# MB_Conn.net
KiCad netlist of a schematic drawn in Altium Designer
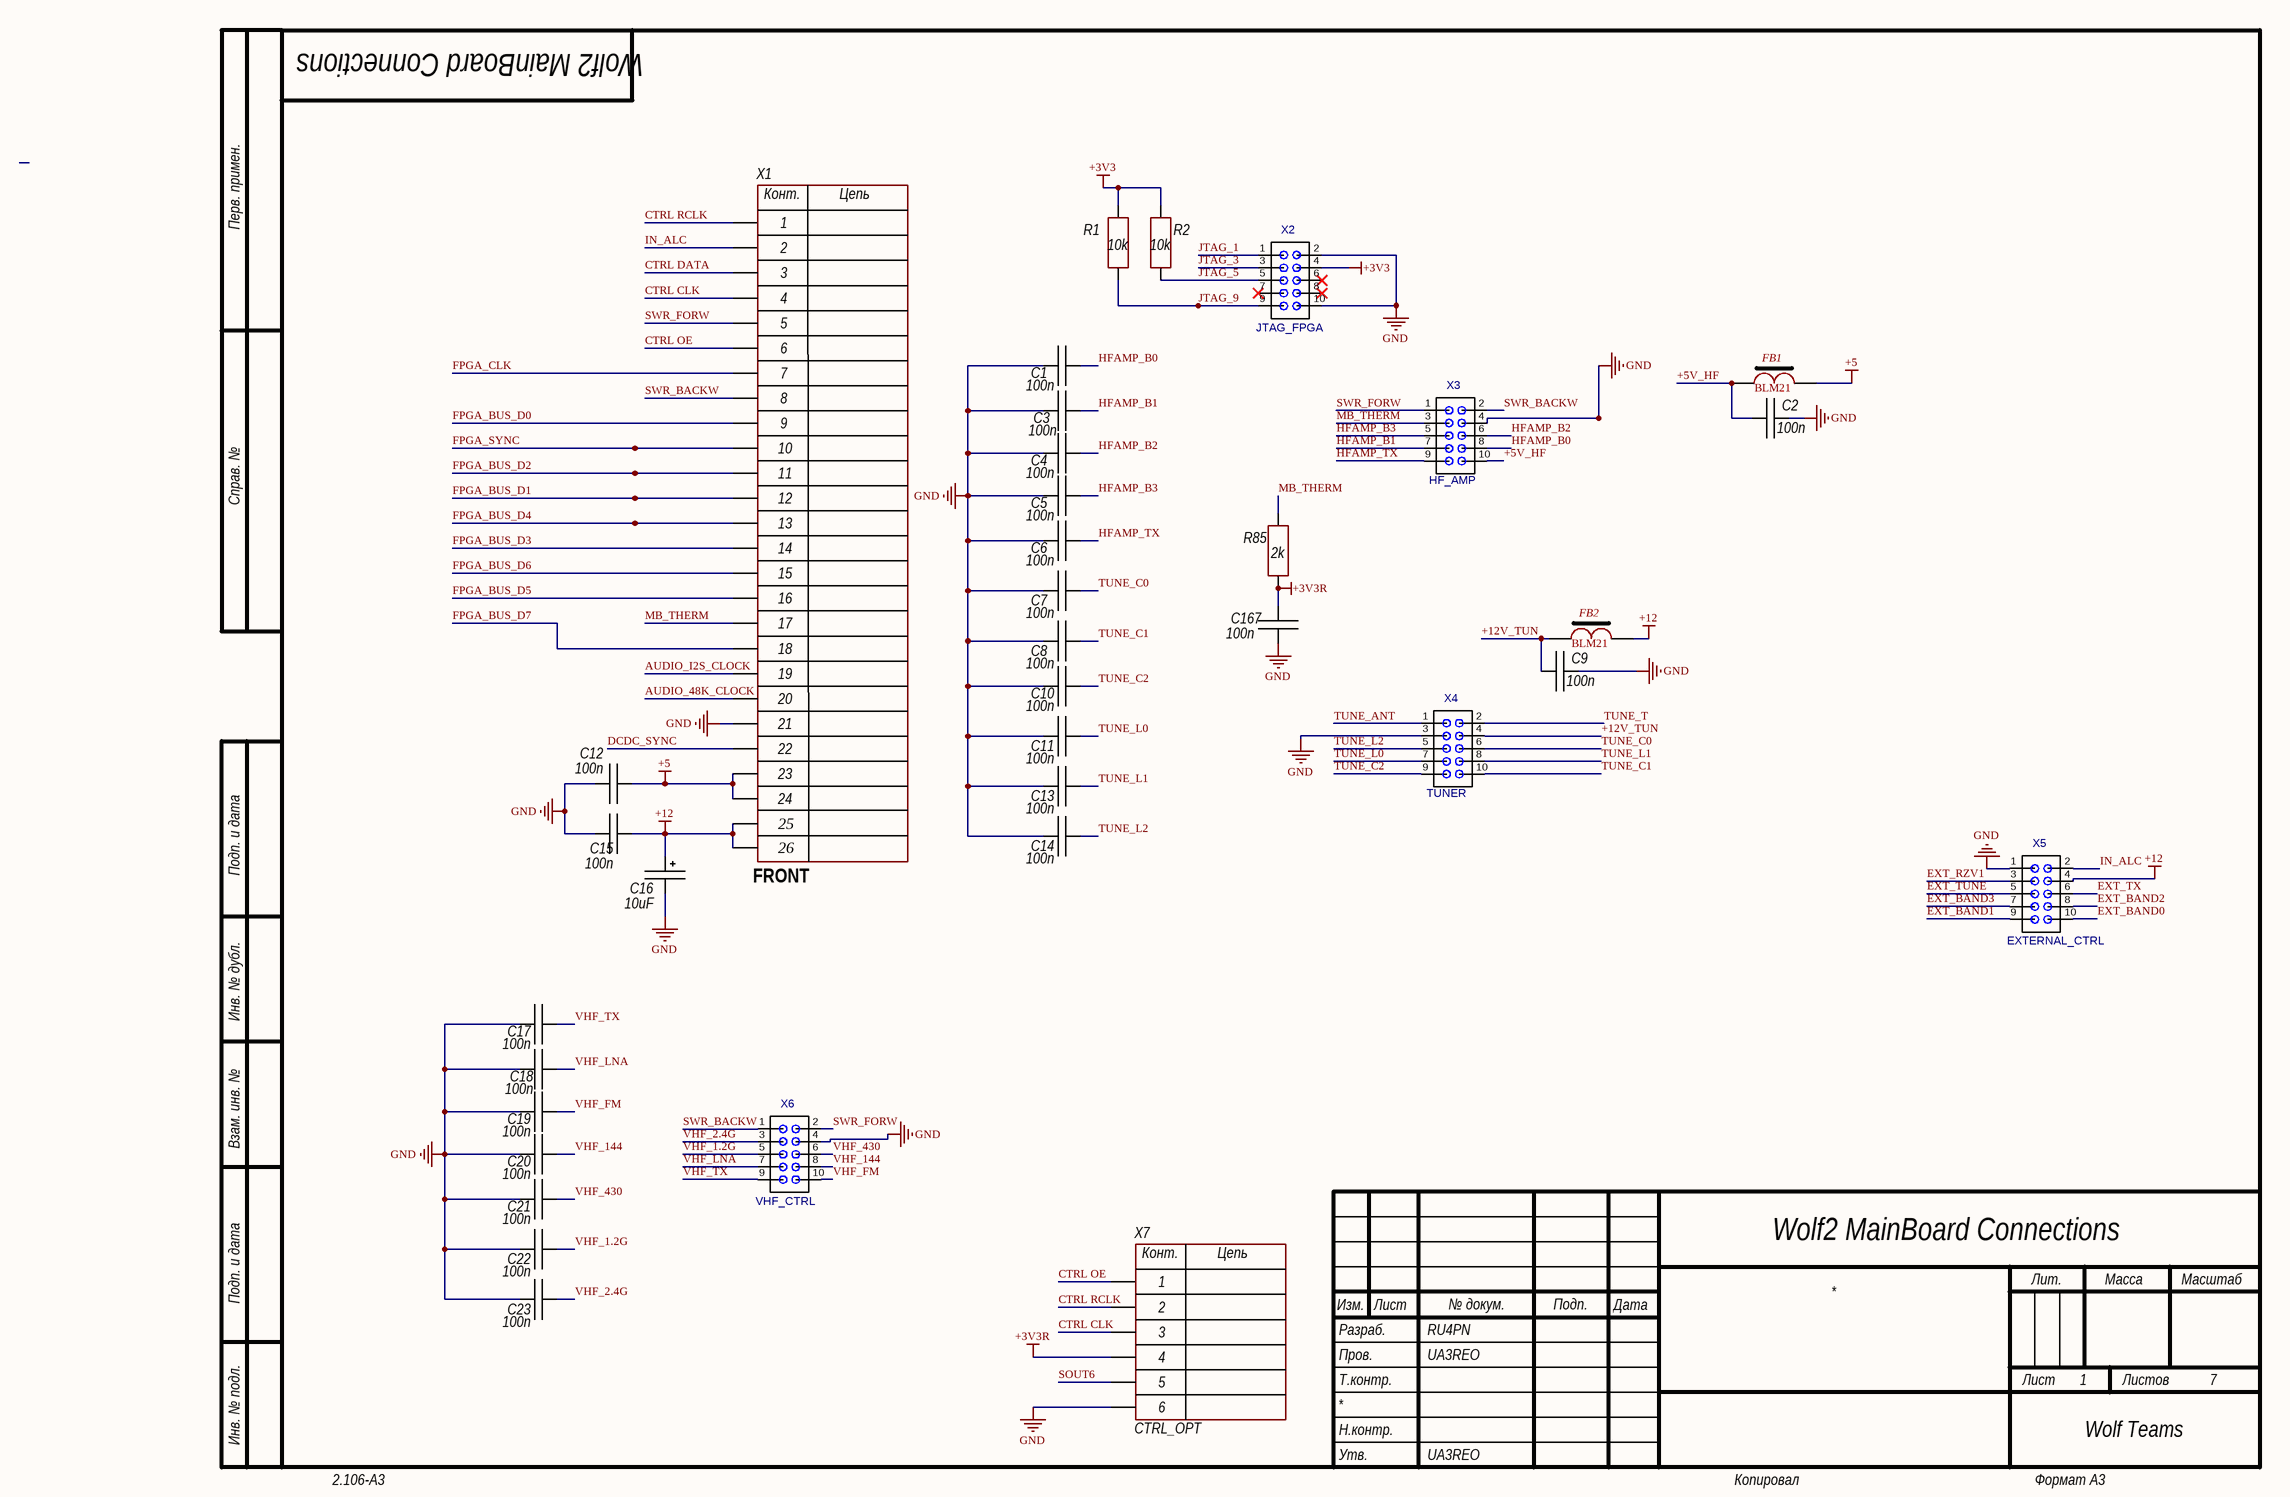
[diagram p0: MB_Conn.SchDoc]

(export (version "E")
  (design (tool "Eeschema 10.0.6"))
  (components
    (comp (ref "C1")
      (value "100n")
      (footprint "standard:CH0805C")
      (libsource (lib "Discrete") (part "Capacitor"))
    )
    (comp (ref "C2")
      (value "100n")
      (footprint "standard:CH0805C")
      (libsource (lib "Discrete") (part "Capacitor"))
    )
    (comp (ref "C3")
      (value "100n")
      (footprint "standard:CH0805C")
      (libsource (lib "Discrete") (part "Capacitor"))
    )
    (comp (ref "C4")
      (value "100n")
      (footprint "standard:CH0805C")
      (libsource (lib "Discrete") (part "Capacitor"))
    )
    (comp (ref "C5")
      (value "100n")
      (footprint "standard:CH0805C")
      (libsource (lib "Discrete") (part "Capacitor"))
    )
    (comp (ref "C6")
      (value "100n")
      (footprint "standard:CH0805C")
      (libsource (lib "Discrete") (part "Capacitor"))
    )
    (comp (ref "C7")
      (value "100n")
      (footprint "standard:CH0805C")
      (libsource (lib "Discrete") (part "Capacitor"))
    )
    (comp (ref "C8")
      (value "100n")
      (footprint "standard:CH0805C")
      (libsource (lib "Discrete") (part "Capacitor"))
    )
    (comp (ref "C9")
      (value "100n")
      (footprint "standard:CH0805C")
      (libsource (lib "Discrete") (part "Capacitor"))
    )
    (comp (ref "C10")
      (value "100n")
      (footprint "standard:CH0805C")
      (libsource (lib "Discrete") (part "Capacitor"))
    )
    (comp (ref "C11")
      (value "100n")
      (footprint "standard:CH0805C")
      (libsource (lib "Discrete") (part "Capacitor"))
    )
    (comp (ref "C12")
      (value "100n")
      (footprint "standard:CH0805C")
      (libsource (lib "Discrete") (part "Capacitor"))
    )
    (comp (ref "C13")
      (value "100n")
      (footprint "standard:CH0805C")
      (libsource (lib "Discrete") (part "Capacitor"))
    )
    (comp (ref "C14")
      (value "100n")
      (footprint "standard:CH0805C")
      (libsource (lib "Discrete") (part "Capacitor"))
    )
    (comp (ref "C15")
      (value "100n")
      (footprint "standard:CH0805C")
      (libsource (lib "Discrete") (part "Capacitor"))
    )
    (comp (ref "C16")
      (value "10uF")
      (footprint "standard:TANTAL_B")
      (libsource (lib "Discrete") (part "TantalCap"))
    )
    (comp (ref "C17")
      (value "100n")
      (footprint "standard:CH0805C")
      (libsource (lib "Discrete") (part "Capacitor"))
    )
    (comp (ref "C18")
      (value "100n")
      (footprint "standard:CH0805C")
      (libsource (lib "Discrete") (part "Capacitor"))
    )
    (comp (ref "C19")
      (value "100n")
      (footprint "standard:CH0805C")
      (libsource (lib "Discrete") (part "Capacitor"))
    )
    (comp (ref "C20")
      (value "100n")
      (footprint "standard:CH0805C")
      (libsource (lib "Discrete") (part "Capacitor"))
    )
    (comp (ref "C21")
      (value "100n")
      (footprint "standard:CH0805C")
      (libsource (lib "Discrete") (part "Capacitor"))
    )
    (comp (ref "C22")
      (value "100n")
      (footprint "standard:CH0805C")
      (libsource (lib "Discrete") (part "Capacitor"))
    )
    (comp (ref "C23")
      (value "100n")
      (footprint "standard:CH0805C")
      (libsource (lib "Discrete") (part "Capacitor"))
    )
    (comp (ref "C167")
      (value "100n")
      (footprint "standard:CH0805C")
      (libsource (lib "Discrete") (part "Capacitor"))
    )
    (comp (ref "FB1") (value "BLM21") (footprint "CH0805L") (libsource (lib "Discrete") (part "FB-1")))
    (comp (ref "FB2") (value "BLM21") (footprint "CH0805L") (libsource (lib "Discrete") (part "FB-1")))
    (comp (ref "R1") (value "10k") (footprint "standard:CH0805R") (libsource (lib "") (part "Resistor_1")))
    (comp (ref "R2") (value "10k") (footprint "standard:CH0805R") (libsource (lib "") (part "Resistor_1")))
    (comp (ref "R85")
      (value "2k")
      (footprint "standard:CH0805R")
      (libsource (lib "Discrete") (part "Resistor"))
    )
    (comp (ref "X1")
      (value "FRONT")
      (footprint "CON: IDC-26")
      (libsource (lib "Connectors") (part "26-Connector"))
    )
    (comp (ref "X2")
      (value "JTAG_FPGA")
      (footprint "CON: BH-10")
      (description "2*5 Pin")
      (libsource (lib "*") (part "IDC10"))
    )
    (comp (ref "X3")
      (value "HF_AMP")
      (footprint "CON: BH-10")
      (description "2*5 Pin")
      (libsource (lib "*") (part "IDC10"))
    )
    (comp (ref "X4")
      (value "TUNER")
      (footprint "CON: BH-10")
      (description "2*5 Pin")
      (libsource (lib "*") (part "IDC10"))
    )
    (comp (ref "X5")
      (value "EXTERNAL_CTRL")
      (footprint "CON: BH-10")
      (description "2*5 Pin")
      (libsource (lib "*") (part "IDC10"))
    )
    (comp (ref "X6")
      (value "VHF_CTRL")
      (footprint "CON: BH-10")
      (description "2*5 Pin")
      (libsource (lib "*") (part "IDC10"))
    )
    (comp (ref "X7")
      (value "CTRL_OPT")
      (footprint "custom:CON: PBS-6")
      (libsource (lib "Connectors") (part "6-Connector"))
    )
  )
  (nets
    (net (code "1") (name "+3V3") (class "Default")
      (node (ref "R1") (pin "2") (pinfunction "2_2") (pintype "passive"))
      (node (ref "R2") (pin "2") (pinfunction "2_2") (pintype "passive"))
      (node (ref "X2") (pin "4") (pinfunction "4_4") (pintype "passive"))
    )
    (net (code "2") (name "+3V3R") (class "Default")
      (node (ref "C167") (pin "2") (pinfunction "2_2") (pintype "power_in"))
      (node (ref "R85") (pin "1") (pinfunction "1_1") (pintype "passive"))
      (node (ref "X7") (pin "4") (pinfunction "4_4") (pintype "power_in"))
    )
    (net (code "3") (name "+5") (class "Default")
      (node (ref "C12") (pin "1") (pinfunction "1_1") (pintype "power_in"))
      (node (ref "FB1") (pin "1") (pinfunction "1_1") (pintype "passive"))
      (node (ref "X1") (pin "23") (pinfunction "23_23") (pintype "power_in"))
      (node (ref "X1") (pin "24") (pinfunction "24_24") (pintype "power_in"))
    )
    (net (code "4") (name "+12") (class "Default")
      (node (ref "C15") (pin "1") (pinfunction "1_1") (pintype "power_in"))
      (node (ref "C16") (pin "1") (pinfunction "1_1") (pintype "power_in"))
      (node (ref "FB2") (pin "1") (pinfunction "1_1") (pintype "passive"))
      (node (ref "X1") (pin "25") (pinfunction "25_25") (pintype "power_in"))
      (node (ref "X1") (pin "26") (pinfunction "26_26") (pintype "passive"))
      (node (ref "X5") (pin "4") (pinfunction "4_4") (pintype "passive"))
    )
    (net (code "5") (name "/+5V_HF") (class "Default")
      (node (ref "C2") (pin "1") (pinfunction "1_1") (pintype "power_in"))
      (node (ref "FB1") (pin "2") (pinfunction "2_2") (pintype "passive"))
      (node (ref "X3") (pin "10") (pinfunction "10_10") (pintype "passive"))
    )
    (net (code "6") (name "/+12V_TUN") (class "Default")
      (node (ref "C9") (pin "1") (pinfunction "1_1") (pintype "power_in"))
      (node (ref "FB2") (pin "2") (pinfunction "2_2") (pintype "passive"))
      (node (ref "X4") (pin "4") (pinfunction "4_4") (pintype "passive"))
    )
    (net (code "7") (name "/AUDIO_48K_CLOCK") (class "Default")
      (node (ref "X1") (pin "20") (pinfunction "20_20") (pintype "power_in"))
    )
    (net (code "8") (name "/AUDIO_I2S_CLOCK") (class "Default")
      (node (ref "X1") (pin "19") (pinfunction "19_19") (pintype "power_in"))
    )
    (net (code "9") (name "/CTRL CLK") (class "Default")
      (node (ref "X1") (pin "4") (pinfunction "4_4") (pintype "power_in"))
      (node (ref "X7") (pin "3") (pinfunction "3_3") (pintype "power_in"))
    )
    (net (code "10") (name "/CTRL DATA") (class "Default")
      (node (ref "X1") (pin "3") (pinfunction "3_3") (pintype "power_in"))
    )
    (net (code "11") (name "/CTRL OE") (class "Default")
      (node (ref "X1") (pin "6") (pinfunction "6_6") (pintype "power_in"))
      (node (ref "X7") (pin "1") (pinfunction "1_1") (pintype "passive"))
    )
    (net (code "12") (name "/CTRL RCLK") (class "Default")
      (node (ref "X1") (pin "1") (pinfunction "1_1") (pintype "passive"))
      (node (ref "X7") (pin "2") (pinfunction "2_2") (pintype "passive"))
    )
    (net (code "13") (name "/DCDC_SYNC") (class "Default")
      (node (ref "X1") (pin "22") (pinfunction "22_22") (pintype "power_in"))
    )
    (net (code "14") (name "/EXT_BAND0") (class "Default")
      (node (ref "X5") (pin "10") (pinfunction "10_10") (pintype "passive"))
    )
    (net (code "15") (name "/EXT_BAND1") (class "Default")
      (node (ref "X5") (pin "9") (pinfunction "9_9") (pintype "passive"))
    )
    (net (code "16") (name "/EXT_BAND2") (class "Default")
      (node (ref "X5") (pin "8") (pinfunction "8_8") (pintype "passive"))
    )
    (net (code "17") (name "/EXT_BAND3") (class "Default")
      (node (ref "X5") (pin "7") (pinfunction "7_7") (pintype "passive"))
    )
    (net (code "18") (name "/EXT_RZV1") (class "Default")
      (node (ref "X5") (pin "3") (pinfunction "3_3") (pintype "passive"))
    )
    (net (code "19") (name "/EXT_TUNE") (class "Default")
      (node (ref "X5") (pin "5") (pinfunction "5_5") (pintype "passive"))
    )
    (net (code "20") (name "/EXT_TX") (class "Default")
      (node (ref "X5") (pin "6") (pinfunction "6_6") (pintype "passive"))
    )
    (net (code "21") (name "/FPGA_BUS_D0") (class "Default")
      (node (ref "X1") (pin "9") (pinfunction "9_9") (pintype "power_in"))
    )
    (net (code "22") (name "/FPGA_BUS_D1") (class "Default")
      (node (ref "X1") (pin "12") (pinfunction "12_12") (pintype "power_in"))
    )
    (net (code "23") (name "/FPGA_BUS_D2") (class "Default")
      (node (ref "X1") (pin "11") (pinfunction "11_11") (pintype "power_in"))
    )
    (net (code "24") (name "/FPGA_BUS_D3") (class "Default")
      (node (ref "X1") (pin "14") (pinfunction "14_14") (pintype "power_in"))
    )
    (net (code "25") (name "/FPGA_BUS_D4") (class "Default")
      (node (ref "X1") (pin "13") (pinfunction "13_13") (pintype "power_in"))
    )
    (net (code "26") (name "/FPGA_BUS_D5") (class "Default")
      (node (ref "X1") (pin "16") (pinfunction "16_16") (pintype "power_in"))
    )
    (net (code "27") (name "/FPGA_BUS_D6") (class "Default")
      (node (ref "X1") (pin "15") (pinfunction "15_15") (pintype "power_in"))
    )
    (net (code "28") (name "/FPGA_BUS_D7") (class "Default")
      (node (ref "X1") (pin "18") (pinfunction "18_18") (pintype "power_in"))
    )
    (net (code "29") (name "/FPGA_CLK") (class "Default")
      (node (ref "X1") (pin "7") (pinfunction "7_7") (pintype "power_in"))
    )
    (net (code "30") (name "/FPGA_SYNC") (class "Default")
      (node (ref "X1") (pin "10") (pinfunction "10_10") (pintype "power_in"))
    )
    (net (code "31") (name "/HFAMP_B0") (class "Default")
      (node (ref "C1") (pin "1") (pinfunction "1_1") (pintype "power_in"))
      (node (ref "X3") (pin "8") (pinfunction "8_8") (pintype "passive"))
    )
    (net (code "32") (name "/HFAMP_B1") (class "Default")
      (node (ref "C3") (pin "1") (pinfunction "1_1") (pintype "power_in"))
      (node (ref "X3") (pin "7") (pinfunction "7_7") (pintype "passive"))
    )
    (net (code "33") (name "/HFAMP_B2") (class "Default")
      (node (ref "C4") (pin "1") (pinfunction "1_1") (pintype "power_in"))
      (node (ref "X3") (pin "6") (pinfunction "6_6") (pintype "passive"))
    )
    (net (code "34") (name "/HFAMP_B3") (class "Default")
      (node (ref "C5") (pin "1") (pinfunction "1_1") (pintype "power_in"))
      (node (ref "X3") (pin "5") (pinfunction "5_5") (pintype "passive"))
    )
    (net (code "35") (name "/HFAMP_TX") (class "Default")
      (node (ref "C6") (pin "1") (pinfunction "1_1") (pintype "power_in"))
      (node (ref "X3") (pin "9") (pinfunction "9_9") (pintype "passive"))
    )
    (net (code "36") (name "/IN_ALC") (class "Default")
      (node (ref "X1") (pin "2") (pinfunction "2_2") (pintype "passive"))
      (node (ref "X5") (pin "2") (pinfunction "2_2") (pintype "passive"))
    )
    (net (code "37") (name "/JTAG_1") (class "Default")
      (node (ref "X2") (pin "1") (pinfunction "1_1") (pintype "passive"))
    )
    (net (code "38") (name "/JTAG_3") (class "Default")
      (node (ref "X2") (pin "3") (pinfunction "3_3") (pintype "passive"))
    )
    (net (code "39") (name "/JTAG_5") (class "Default")
      (node (ref "R2") (pin "1") (pinfunction "1_1") (pintype "passive"))
      (node (ref "X2") (pin "5") (pinfunction "5_5") (pintype "passive"))
    )
    (net (code "40") (name "/JTAG_9") (class "Default")
      (node (ref "R1") (pin "1") (pinfunction "1_1") (pintype "passive"))
      (node (ref "X2") (pin "9") (pinfunction "9_9") (pintype "passive"))
    )
    (net (code "41") (name "/MB_THERM") (class "Default")
      (node (ref "R85") (pin "2") (pinfunction "2_2") (pintype "passive"))
      (node (ref "X1") (pin "17") (pinfunction "17_17") (pintype "power_in"))
      (node (ref "X3") (pin "3") (pinfunction "3_3") (pintype "passive"))
    )
    (net (code "42") (name "/SOUT6") (class "Default")
      (node (ref "X7") (pin "5") (pinfunction "5_5") (pintype "power_in"))
    )
    (net (code "43") (name "/SWR_BACKW") (class "Default")
      (node (ref "X1") (pin "8") (pinfunction "8_8") (pintype "power_in"))
      (node (ref "X3") (pin "2") (pinfunction "2_2") (pintype "passive"))
      (node (ref "X6") (pin "1") (pinfunction "1_1") (pintype "passive"))
    )
    (net (code "44") (name "/SWR_FORW") (class "Default")
      (node (ref "X1") (pin "5") (pinfunction "5_5") (pintype "power_in"))
      (node (ref "X3") (pin "1") (pinfunction "1_1") (pintype "passive"))
      (node (ref "X6") (pin "2") (pinfunction "2_2") (pintype "passive"))
    )
    (net (code "45") (name "/TUNE_ANT") (class "Default")
      (node (ref "X4") (pin "1") (pinfunction "1_1") (pintype "passive"))
    )
    (net (code "46") (name "/TUNE_C0") (class "Default")
      (node (ref "C7") (pin "1") (pinfunction "1_1") (pintype "power_in"))
      (node (ref "X4") (pin "6") (pinfunction "6_6") (pintype "passive"))
    )
    (net (code "47") (name "/TUNE_C1") (class "Default")
      (node (ref "C8") (pin "1") (pinfunction "1_1") (pintype "power_in"))
      (node (ref "X4") (pin "10") (pinfunction "10_10") (pintype "passive"))
    )
    (net (code "48") (name "/TUNE_C2") (class "Default")
      (node (ref "C10") (pin "1") (pinfunction "1_1") (pintype "power_in"))
      (node (ref "X4") (pin "9") (pinfunction "9_9") (pintype "passive"))
    )
    (net (code "49") (name "/TUNE_L0") (class "Default")
      (node (ref "C11") (pin "1") (pinfunction "1_1") (pintype "power_in"))
      (node (ref "X4") (pin "7") (pinfunction "7_7") (pintype "passive"))
    )
    (net (code "50") (name "/TUNE_L1") (class "Default")
      (node (ref "C13") (pin "1") (pinfunction "1_1") (pintype "power_in"))
      (node (ref "X4") (pin "8") (pinfunction "8_8") (pintype "passive"))
    )
    (net (code "51") (name "/TUNE_L2") (class "Default")
      (node (ref "C14") (pin "1") (pinfunction "1_1") (pintype "power_in"))
      (node (ref "X4") (pin "5") (pinfunction "5_5") (pintype "passive"))
    )
    (net (code "52") (name "/TUNE_T") (class "Default")
      (node (ref "X4") (pin "2") (pinfunction "2_2") (pintype "passive"))
    )
    (net (code "53") (name "/VHF_1.2G") (class "Default")
      (node (ref "C22") (pin "1") (pinfunction "1_1") (pintype "power_in"))
      (node (ref "X6") (pin "5") (pinfunction "5_5") (pintype "passive"))
    )
    (net (code "54") (name "/VHF_2.4G") (class "Default")
      (node (ref "C23") (pin "1") (pinfunction "1_1") (pintype "power_in"))
      (node (ref "X6") (pin "3") (pinfunction "3_3") (pintype "passive"))
    )
    (net (code "55") (name "/VHF_144") (class "Default")
      (node (ref "C20") (pin "1") (pinfunction "1_1") (pintype "power_in"))
      (node (ref "X6") (pin "8") (pinfunction "8_8") (pintype "passive"))
    )
    (net (code "56") (name "/VHF_430") (class "Default")
      (node (ref "C21") (pin "1") (pinfunction "1_1") (pintype "power_in"))
      (node (ref "X6") (pin "6") (pinfunction "6_6") (pintype "passive"))
    )
    (net (code "57") (name "/VHF_FM") (class "Default")
      (node (ref "C19") (pin "1") (pinfunction "1_1") (pintype "power_in"))
      (node (ref "X6") (pin "10") (pinfunction "10_10") (pintype "passive"))
    )
    (net (code "58") (name "/VHF_LNA") (class "Default")
      (node (ref "C18") (pin "1") (pinfunction "1_1") (pintype "power_in"))
      (node (ref "X6") (pin "7") (pinfunction "7_7") (pintype "passive"))
    )
    (net (code "59") (name "/VHF_TX") (class "Default")
      (node (ref "C17") (pin "1") (pinfunction "1_1") (pintype "power_in"))
      (node (ref "X6") (pin "9") (pinfunction "9_9") (pintype "passive"))
    )
    (net (code "60") (name "GND") (class "Default")
      (node (ref "C1") (pin "2") (pinfunction "2_2") (pintype "power_in"))
      (node (ref "C10") (pin "2") (pinfunction "2_2") (pintype "power_in"))
      (node (ref "C11") (pin "2") (pinfunction "2_2") (pintype "power_in"))
      (node (ref "C12") (pin "2") (pinfunction "2_2") (pintype "power_in"))
      (node (ref "C13") (pin "2") (pinfunction "2_2") (pintype "power_in"))
      (node (ref "C14") (pin "2") (pinfunction "2_2") (pintype "power_in"))
      (node (ref "C15") (pin "2") (pinfunction "2_2") (pintype "power_in"))
      (node (ref "C16") (pin "2") (pinfunction "2_2") (pintype "power_in"))
      (node (ref "C167") (pin "1") (pinfunction "1_1") (pintype "power_in"))
      (node (ref "C17") (pin "2") (pinfunction "2_2") (pintype "power_in"))
      (node (ref "C18") (pin "2") (pinfunction "2_2") (pintype "power_in"))
      (node (ref "C19") (pin "2") (pinfunction "2_2") (pintype "power_in"))
      (node (ref "C2") (pin "2") (pinfunction "2_2") (pintype "power_in"))
      (node (ref "C20") (pin "2") (pinfunction "2_2") (pintype "power_in"))
      (node (ref "C21") (pin "2") (pinfunction "2_2") (pintype "power_in"))
      (node (ref "C22") (pin "2") (pinfunction "2_2") (pintype "power_in"))
      (node (ref "C23") (pin "2") (pinfunction "2_2") (pintype "power_in"))
      (node (ref "C3") (pin "2") (pinfunction "2_2") (pintype "power_in"))
      (node (ref "C4") (pin "2") (pinfunction "2_2") (pintype "power_in"))
      (node (ref "C5") (pin "2") (pinfunction "2_2") (pintype "power_in"))
      (node (ref "C6") (pin "2") (pinfunction "2_2") (pintype "power_in"))
      (node (ref "C7") (pin "2") (pinfunction "2_2") (pintype "power_in"))
      (node (ref "C8") (pin "2") (pinfunction "2_2") (pintype "power_in"))
      (node (ref "C9") (pin "2") (pinfunction "2_2") (pintype "power_in"))
      (node (ref "X1") (pin "21") (pinfunction "21_21") (pintype "power_in"))
      (node (ref "X2") (pin "10") (pinfunction "10_10") (pintype "passive"))
      (node (ref "X2") (pin "2") (pinfunction "2_2") (pintype "passive"))
      (node (ref "X3") (pin "4") (pinfunction "4_4") (pintype "passive"))
      (node (ref "X4") (pin "3") (pinfunction "3_3") (pintype "passive"))
      (node (ref "X5") (pin "1") (pinfunction "1_1") (pintype "passive"))
      (node (ref "X6") (pin "4") (pinfunction "4_4") (pintype "passive"))
      (node (ref "X7") (pin "6") (pinfunction "6_6") (pintype "power_in"))
    )
    (net (code "61") (name "unconnected-(X2-Pad6)") (class "Default")
      (node (ref "X2") (pin "6") (pinfunction "6_6") (pintype "passive+no_connect"))
    )
    (net (code "62") (name "unconnected-(X2-Pad7)") (class "Default")
      (node (ref "X2") (pin "7") (pinfunction "7_7") (pintype "passive+no_connect"))
    )
    (net (code "63") (name "unconnected-(X2-Pad8)") (class "Default")
      (node (ref "X2") (pin "8") (pinfunction "8_8") (pintype "passive+no_connect"))
    )
  )
)
